# 4_underglow.net
KiCad netlist of a schematic drawn in Altium Designer
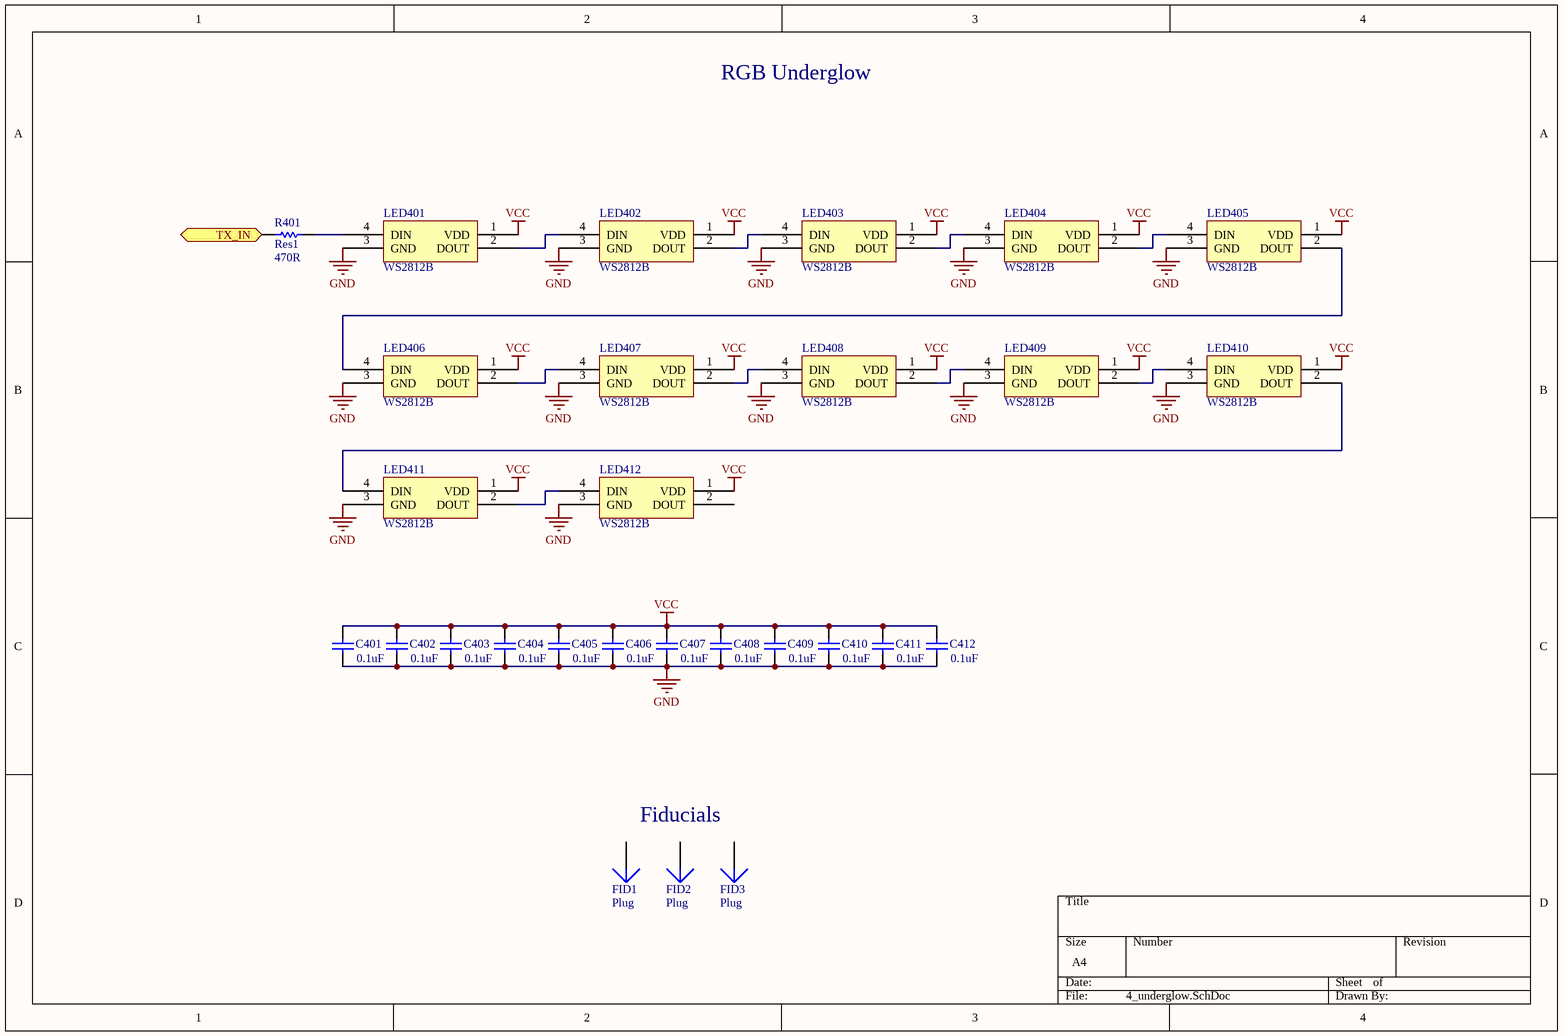
[diagram p0: 4_underglow.SchDoc]

(export (version "E")
  (design (tool "Eeschema 10.0.6"))
  (components
    (comp (ref "C401")
      (value "0.1uF")
      (footprint "C0603[1608]")
      (description "Capacitor")
      (fields (field (name "MFG") "KEMET") (field (name "MRF.PART") "CC0603KRX7R9BB104"))
      (libsource (lib "Miscellaneous Devices") (part "Cap"))
    )
    (comp (ref "C402")
      (value "0.1uF")
      (footprint "C0603[1608]")
      (description "Capacitor")
      (fields (field (name "MFG") "KEMET") (field (name "MRF.PART") "CC0603KRX7R9BB104"))
      (libsource (lib "Miscellaneous Devices") (part "Cap"))
    )
    (comp (ref "C403")
      (value "0.1uF")
      (footprint "C0603[1608]")
      (description "Capacitor")
      (fields (field (name "MFG") "KEMET") (field (name "MRF.PART") "CC0603KRX7R9BB104"))
      (libsource (lib "Miscellaneous Devices") (part "Cap"))
    )
    (comp (ref "C404")
      (value "0.1uF")
      (footprint "C0603[1608]")
      (description "Capacitor")
      (fields (field (name "MFG") "KEMET") (field (name "MRF.PART") "CC0603KRX7R9BB104"))
      (libsource (lib "Miscellaneous Devices") (part "Cap"))
    )
    (comp (ref "C405")
      (value "0.1uF")
      (footprint "C0603[1608]")
      (description "Capacitor")
      (fields (field (name "MFG") "KEMET") (field (name "MRF.PART") "CC0603KRX7R9BB104"))
      (libsource (lib "Miscellaneous Devices") (part "Cap"))
    )
    (comp (ref "C406")
      (value "0.1uF")
      (footprint "C0603[1608]")
      (description "Capacitor")
      (fields (field (name "MFG") "KEMET") (field (name "MRF.PART") "CC0603KRX7R9BB104"))
      (libsource (lib "Miscellaneous Devices") (part "Cap"))
    )
    (comp (ref "C407")
      (value "0.1uF")
      (footprint "C0603[1608]")
      (description "Capacitor")
      (fields (field (name "MFG") "KEMET") (field (name "MRF.PART") "CC0603KRX7R9BB104"))
      (libsource (lib "Miscellaneous Devices") (part "Cap"))
    )
    (comp (ref "C408")
      (value "0.1uF")
      (footprint "C0603[1608]")
      (description "Capacitor")
      (fields (field (name "MFG") "KEMET") (field (name "MRF.PART") "CC0603KRX7R9BB104"))
      (libsource (lib "Miscellaneous Devices") (part "Cap"))
    )
    (comp (ref "C409")
      (value "0.1uF")
      (footprint "C0603[1608]")
      (description "Capacitor")
      (fields (field (name "MFG") "KEMET") (field (name "MRF.PART") "CC0603KRX7R9BB104"))
      (libsource (lib "Miscellaneous Devices") (part "Cap"))
    )
    (comp (ref "C410")
      (value "0.1uF")
      (footprint "C0603[1608]")
      (description "Capacitor")
      (fields (field (name "MFG") "KEMET") (field (name "MRF.PART") "CC0603KRX7R9BB104"))
      (libsource (lib "Miscellaneous Devices") (part "Cap"))
    )
    (comp (ref "C411")
      (value "0.1uF")
      (footprint "C0603[1608]")
      (description "Capacitor")
      (fields (field (name "MFG") "KEMET") (field (name "MRF.PART") "CC0603KRX7R9BB104"))
      (libsource (lib "Miscellaneous Devices") (part "Cap"))
    )
    (comp (ref "C412")
      (value "0.1uF")
      (footprint "C0603[1608]")
      (description "Capacitor")
      (fields (field (name "MFG") "KEMET") (field (name "MRF.PART") "CC0603KRX7R9BB104"))
      (libsource (lib "Miscellaneous Devices") (part "Cap"))
    )
    (comp (ref "FID1")
      (value "Plug")
      (footprint "Fiducial_Nordic")
      (libsource (lib "Miscellaneous Connectors") (part "Plug"))
    )
    (comp (ref "FID2")
      (value "Plug")
      (footprint "Fiducial_Nordic")
      (libsource (lib "Miscellaneous Connectors") (part "Plug"))
    )
    (comp (ref "FID3")
      (value "Plug")
      (footprint "Fiducial_Nordic")
      (libsource (lib "Miscellaneous Connectors") (part "Plug"))
    )
    (comp (ref "LED401")
      (value "WS2812B")
      (footprint "WS2812B")
      (fields (field (name "MRF.PART") "WS2812B-B"))
      (libsource (lib "Keebs") (part "WS2812B"))
    )
    (comp (ref "LED402")
      (value "WS2812B")
      (footprint "WS2812B")
      (fields (field (name "MRF.PART") "WS2812B-B"))
      (libsource (lib "Keebs") (part "WS2812B"))
    )
    (comp (ref "LED403")
      (value "WS2812B")
      (footprint "WS2812B")
      (fields (field (name "MRF.PART") "WS2812B-B"))
      (libsource (lib "Keebs") (part "WS2812B"))
    )
    (comp (ref "LED404")
      (value "WS2812B")
      (footprint "WS2812B")
      (fields (field (name "MRF.PART") "WS2812B-B"))
      (libsource (lib "Keebs") (part "WS2812B"))
    )
    (comp (ref "LED405")
      (value "WS2812B")
      (footprint "WS2812B")
      (fields (field (name "MRF.PART") "WS2812B-B"))
      (libsource (lib "Keebs") (part "WS2812B"))
    )
    (comp (ref "LED406")
      (value "WS2812B")
      (footprint "WS2812B")
      (fields (field (name "MRF.PART") "WS2812B-B"))
      (libsource (lib "Keebs") (part "WS2812B"))
    )
    (comp (ref "LED407")
      (value "WS2812B")
      (footprint "WS2812B")
      (fields (field (name "MRF.PART") "WS2812B-B"))
      (libsource (lib "Keebs") (part "WS2812B"))
    )
    (comp (ref "LED408")
      (value "WS2812B")
      (footprint "WS2812B")
      (fields (field (name "MRF.PART") "WS2812B-B"))
      (libsource (lib "Keebs") (part "WS2812B"))
    )
    (comp (ref "LED409")
      (value "WS2812B")
      (footprint "WS2812B")
      (fields (field (name "MRF.PART") "WS2812B-B"))
      (libsource (lib "Keebs") (part "WS2812B"))
    )
    (comp (ref "LED410")
      (value "WS2812B")
      (footprint "WS2812B")
      (fields (field (name "MRF.PART") "WS2812B-B"))
      (libsource (lib "Keebs") (part "WS2812B"))
    )
    (comp (ref "LED411")
      (value "WS2812B")
      (footprint "WS2812B")
      (fields (field (name "MRF.PART") "WS2812B-B"))
      (libsource (lib "Keebs") (part "WS2812B"))
    )
    (comp (ref "LED412")
      (value "WS2812B")
      (footprint "WS2812B")
      (fields (field (name "MRF.PART") "WS2812B-B"))
      (libsource (lib "Keebs") (part "WS2812B"))
    )
    (comp (ref "R401")
      (value "Res1")
      (footprint "R0603[1608]")
      (description "Resistor")
      (fields (field (name "ALTIUM_VALUE") "470R") (field (name "MRF.PART") "0603WAF4700T5E"))
      (libsource (lib "Miscellaneous Devices") (part "Res1"))
    )
  )
  (nets
    (net (code "1") (name "/TX_IN") (class "Default")
      (node (ref "R401") (pin "1") (pinfunction "1_1") (pintype "passive"))
    )
    (net (code "2") (name "GND") (class "Default")
      (node (ref "C401") (pin "1") (pinfunction "1_1") (pintype "passive"))
      (node (ref "C402") (pin "1") (pinfunction "1_1") (pintype "passive"))
      (node (ref "C403") (pin "1") (pinfunction "1_1") (pintype "passive"))
      (node (ref "C404") (pin "1") (pinfunction "1_1") (pintype "passive"))
      (node (ref "C405") (pin "1") (pinfunction "1_1") (pintype "passive"))
      (node (ref "C406") (pin "1") (pinfunction "1_1") (pintype "passive"))
      (node (ref "C407") (pin "1") (pinfunction "1_1") (pintype "passive"))
      (node (ref "C408") (pin "1") (pinfunction "1_1") (pintype "passive"))
      (node (ref "C409") (pin "1") (pinfunction "1_1") (pintype "passive"))
      (node (ref "C410") (pin "1") (pinfunction "1_1") (pintype "passive"))
      (node (ref "C411") (pin "1") (pinfunction "1_1") (pintype "passive"))
      (node (ref "C412") (pin "1") (pinfunction "1_1") (pintype "passive"))
      (node (ref "LED401") (pin "3") (pinfunction "GND_3") (pintype "passive"))
      (node (ref "LED402") (pin "3") (pinfunction "GND_3") (pintype "passive"))
      (node (ref "LED403") (pin "3") (pinfunction "GND_3") (pintype "passive"))
      (node (ref "LED404") (pin "3") (pinfunction "GND_3") (pintype "passive"))
      (node (ref "LED405") (pin "3") (pinfunction "GND_3") (pintype "passive"))
      (node (ref "LED406") (pin "3") (pinfunction "GND_3") (pintype "passive"))
      (node (ref "LED407") (pin "3") (pinfunction "GND_3") (pintype "passive"))
      (node (ref "LED408") (pin "3") (pinfunction "GND_3") (pintype "passive"))
      (node (ref "LED409") (pin "3") (pinfunction "GND_3") (pintype "passive"))
      (node (ref "LED410") (pin "3") (pinfunction "GND_3") (pintype "passive"))
      (node (ref "LED411") (pin "3") (pinfunction "GND_3") (pintype "passive"))
      (node (ref "LED412") (pin "3") (pinfunction "GND_3") (pintype "passive"))
    )
    (net (code "3") (name "Net-(LED401-DIN)") (class "Default")
      (node (ref "LED401") (pin "4") (pinfunction "DIN_4") (pintype "passive"))
      (node (ref "R401") (pin "2") (pinfunction "2_2") (pintype "passive"))
    )
    (net (code "4") (name "Net-(LED401-DOUT)") (class "Default")
      (node (ref "LED401") (pin "2") (pinfunction "DOUT_2") (pintype "passive"))
      (node (ref "LED402") (pin "4") (pinfunction "DIN_4") (pintype "passive"))
    )
    (net (code "5") (name "Net-(LED402-DOUT)") (class "Default")
      (node (ref "LED402") (pin "2") (pinfunction "DOUT_2") (pintype "passive"))
      (node (ref "LED403") (pin "4") (pinfunction "DIN_4") (pintype "passive"))
    )
    (net (code "6") (name "Net-(LED403-DOUT)") (class "Default")
      (node (ref "LED403") (pin "2") (pinfunction "DOUT_2") (pintype "passive"))
      (node (ref "LED404") (pin "4") (pinfunction "DIN_4") (pintype "passive"))
    )
    (net (code "7") (name "Net-(LED404-DOUT)") (class "Default")
      (node (ref "LED404") (pin "2") (pinfunction "DOUT_2") (pintype "passive"))
      (node (ref "LED405") (pin "4") (pinfunction "DIN_4") (pintype "passive"))
    )
    (net (code "8") (name "Net-(LED405-DOUT)") (class "Default")
      (node (ref "LED405") (pin "2") (pinfunction "DOUT_2") (pintype "passive"))
      (node (ref "LED406") (pin "4") (pinfunction "DIN_4") (pintype "passive"))
    )
    (net (code "9") (name "Net-(LED406-DOUT)") (class "Default")
      (node (ref "LED406") (pin "2") (pinfunction "DOUT_2") (pintype "passive"))
      (node (ref "LED407") (pin "4") (pinfunction "DIN_4") (pintype "passive"))
    )
    (net (code "10") (name "Net-(LED407-DOUT)") (class "Default")
      (node (ref "LED407") (pin "2") (pinfunction "DOUT_2") (pintype "passive"))
      (node (ref "LED408") (pin "4") (pinfunction "DIN_4") (pintype "passive"))
    )
    (net (code "11") (name "Net-(LED408-DOUT)") (class "Default")
      (node (ref "LED408") (pin "2") (pinfunction "DOUT_2") (pintype "passive"))
      (node (ref "LED409") (pin "4") (pinfunction "DIN_4") (pintype "passive"))
    )
    (net (code "12") (name "Net-(LED409-DOUT)") (class "Default")
      (node (ref "LED409") (pin "2") (pinfunction "DOUT_2") (pintype "passive"))
      (node (ref "LED410") (pin "4") (pinfunction "DIN_4") (pintype "passive"))
    )
    (net (code "13") (name "Net-(LED410-DOUT)") (class "Default")
      (node (ref "LED410") (pin "2") (pinfunction "DOUT_2") (pintype "passive"))
      (node (ref "LED411") (pin "4") (pinfunction "DIN_4") (pintype "passive"))
    )
    (net (code "14") (name "Net-(LED411-DOUT)") (class "Default")
      (node (ref "LED411") (pin "2") (pinfunction "DOUT_2") (pintype "passive"))
      (node (ref "LED412") (pin "4") (pinfunction "DIN_4") (pintype "passive"))
    )
    (net (code "15") (name "VCC") (class "Default")
      (node (ref "C401") (pin "2") (pinfunction "2_2") (pintype "passive"))
      (node (ref "C402") (pin "2") (pinfunction "2_2") (pintype "passive"))
      (node (ref "C403") (pin "2") (pinfunction "2_2") (pintype "passive"))
      (node (ref "C404") (pin "2") (pinfunction "2_2") (pintype "passive"))
      (node (ref "C405") (pin "2") (pinfunction "2_2") (pintype "passive"))
      (node (ref "C406") (pin "2") (pinfunction "2_2") (pintype "passive"))
      (node (ref "C407") (pin "2") (pinfunction "2_2") (pintype "passive"))
      (node (ref "C408") (pin "2") (pinfunction "2_2") (pintype "passive"))
      (node (ref "C409") (pin "2") (pinfunction "2_2") (pintype "passive"))
      (node (ref "C410") (pin "2") (pinfunction "2_2") (pintype "passive"))
      (node (ref "C411") (pin "2") (pinfunction "2_2") (pintype "passive"))
      (node (ref "C412") (pin "2") (pinfunction "2_2") (pintype "passive"))
      (node (ref "LED401") (pin "1") (pinfunction "VDD_1") (pintype "passive"))
      (node (ref "LED402") (pin "1") (pinfunction "VDD_1") (pintype "passive"))
      (node (ref "LED403") (pin "1") (pinfunction "VDD_1") (pintype "passive"))
      (node (ref "LED404") (pin "1") (pinfunction "VDD_1") (pintype "passive"))
      (node (ref "LED405") (pin "1") (pinfunction "VDD_1") (pintype "passive"))
      (node (ref "LED406") (pin "1") (pinfunction "VDD_1") (pintype "passive"))
      (node (ref "LED407") (pin "1") (pinfunction "VDD_1") (pintype "passive"))
      (node (ref "LED408") (pin "1") (pinfunction "VDD_1") (pintype "passive"))
      (node (ref "LED409") (pin "1") (pinfunction "VDD_1") (pintype "passive"))
      (node (ref "LED410") (pin "1") (pinfunction "VDD_1") (pintype "passive"))
      (node (ref "LED411") (pin "1") (pinfunction "VDD_1") (pintype "passive"))
      (node (ref "LED412") (pin "1") (pinfunction "VDD_1") (pintype "passive"))
    )
    (net (code "16") (name "unconnected-(FID1-Pad1)") (class "Default")
      (node (ref "FID1") (pin "1") (pinfunction "1_1") (pintype "passive"))
    )
    (net (code "17") (name "unconnected-(FID2-Pad1)") (class "Default")
      (node (ref "FID2") (pin "1") (pinfunction "1_1") (pintype "passive"))
    )
    (net (code "18") (name "unconnected-(FID3-Pad1)") (class "Default")
      (node (ref "FID3") (pin "1") (pinfunction "1_1") (pintype "passive"))
    )
    (net (code "19") (name "unconnected-(LED412-DOUT-Pad2)") (class "Default")
      (node (ref "LED412") (pin "2") (pinfunction "DOUT_2") (pintype "passive"))
    )
  )
)
